# Adafruit_LSM9DS1_Rev_C.net
KiCad netlist of a schematic drawn in EAGLE
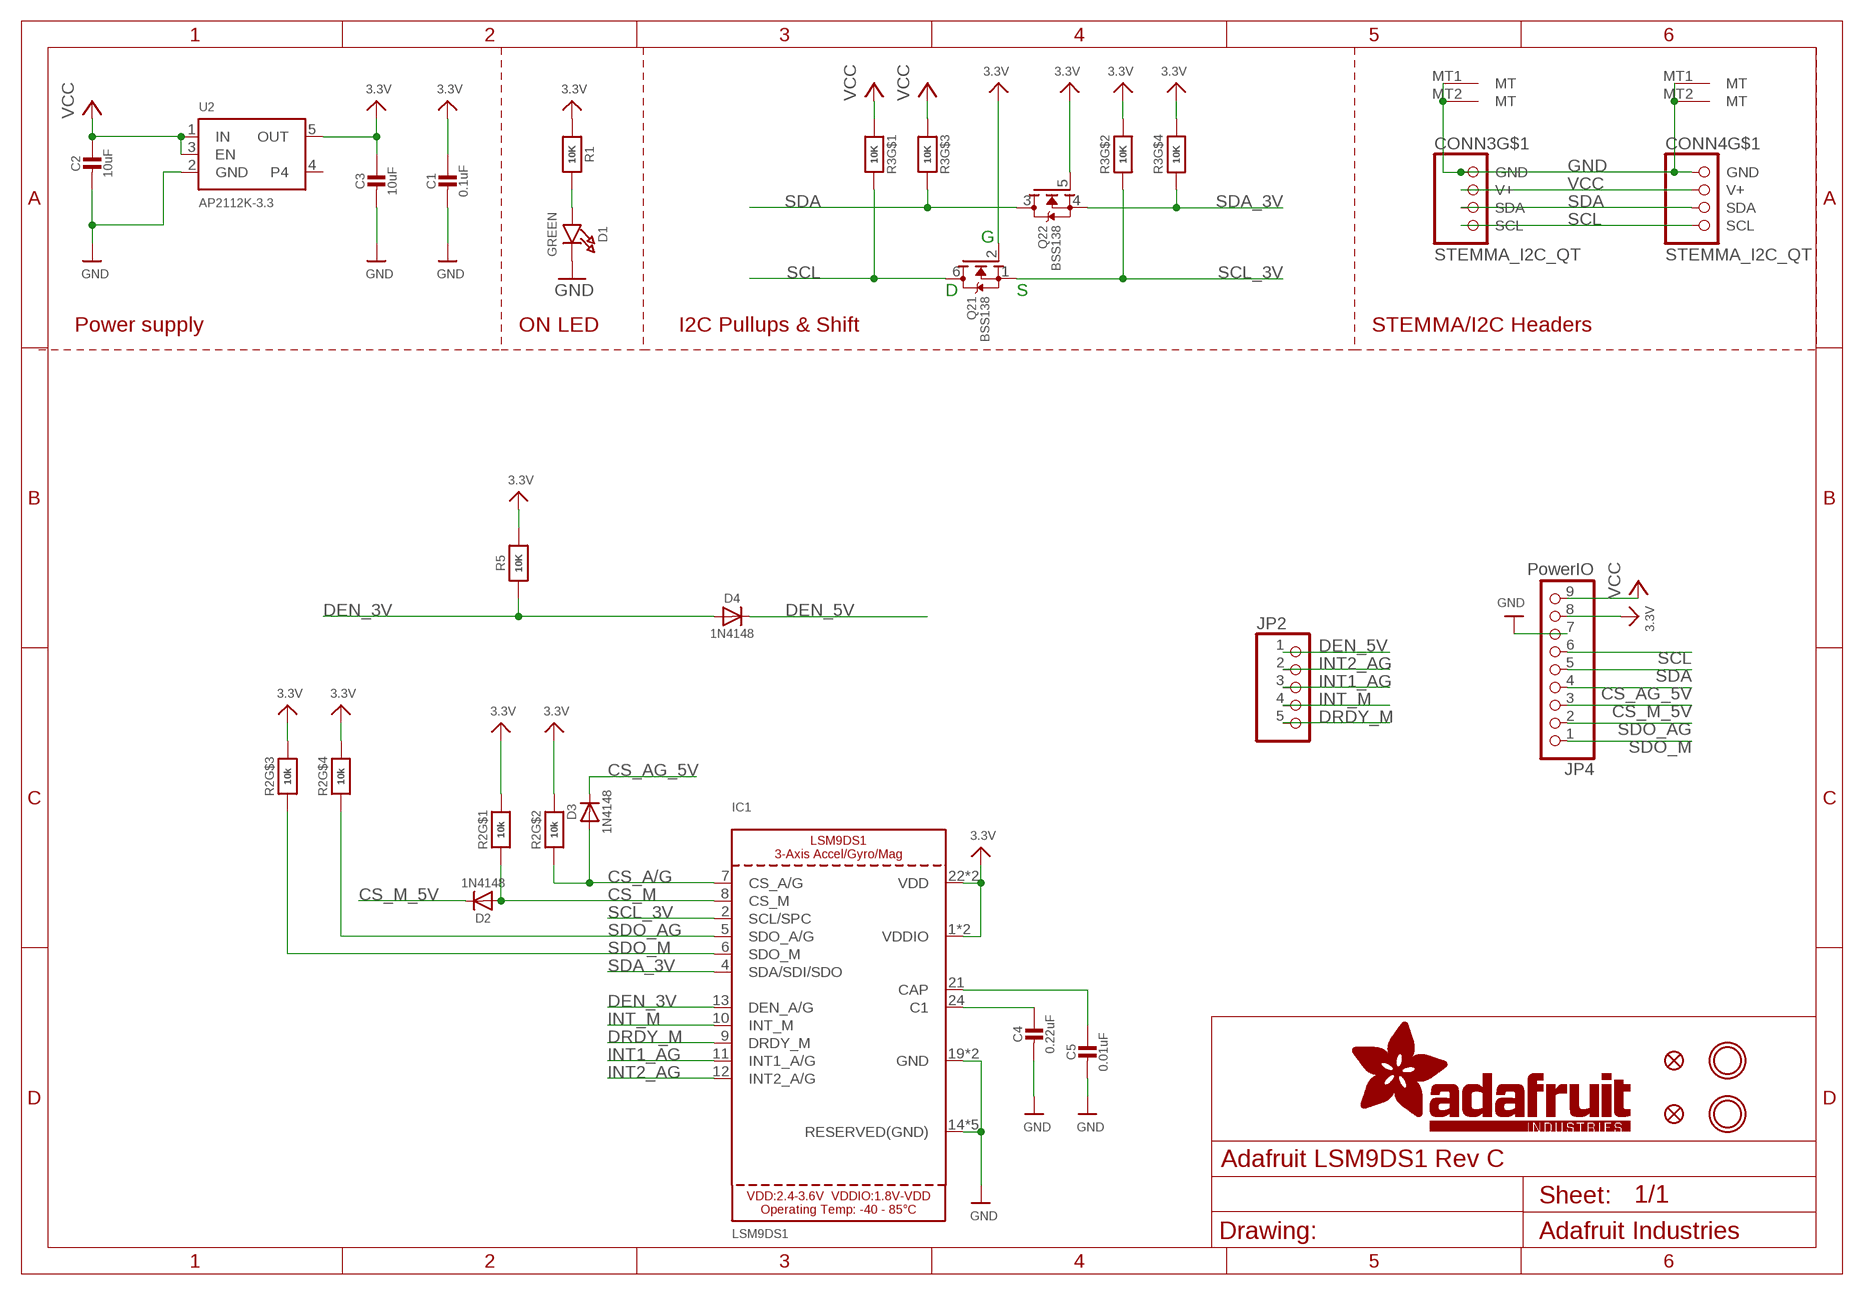
[diagram p0: schematic, sheet 1]

(export (version "E")
  (design (tool "Eeschema 10.0.6"))
  (components
    (comp (ref "C1")
      (value "0.1uF")
      (footprint "eagle-import:0603-NO")
      (libsource (lib "eagle-import") (part "CAP_CERAMIC0603_NO"))
    )
    (comp (ref "C2")
      (value "10uF")
      (footprint "eagle-import:_0805MP")
      (libsource (lib "eagle-import") (part "CAP_CERAMIC_0805MP"))
    )
    (comp (ref "C3")
      (value "10uF")
      (footprint "eagle-import:0805-NO")
      (libsource (lib "eagle-import") (part "CAP_CERAMIC0805-NOOUTLINE"))
    )
    (comp (ref "C4")
      (value "0.22uF")
      (footprint "eagle-import:0603-NO")
      (libsource (lib "eagle-import") (part "CAP_CERAMIC0603_NO"))
    )
    (comp (ref "C5")
      (value "0.01uF")
      (footprint "eagle-import:0603-NO")
      (libsource (lib "eagle-import") (part "CAP_CERAMIC0603_NO"))
    )
    (comp (ref "CONN3")
      (value "STEMMA_I2C_QT")
      (footprint "eagle-import:JST_SH4")
      (libsource (lib "eagle-import") (part "STEMMA_I2C_QT"))
    )
    (comp (ref "CONN4")
      (value "STEMMA_I2C_QT")
      (footprint "eagle-import:JST_SH4")
      (libsource (lib "eagle-import") (part "STEMMA_I2C_QT"))
    )
    (comp (ref "D1")
      (value "GREEN")
      (footprint "eagle-import:CHIPLED_0603_NOOUTLINE")
      (libsource (lib "eagle-import") (part "LED0603_NOOUTLINE"))
    )
    (comp (ref "D2")
      (value "1N4148")
      (footprint "eagle-import:SOD-323")
      (libsource (lib "eagle-import") (part "DIODESOD-323"))
    )
    (comp (ref "D3")
      (value "1N4148")
      (footprint "eagle-import:SOD-323")
      (libsource (lib "eagle-import") (part "DIODESOD-323"))
    )
    (comp (ref "D4")
      (value "1N4148")
      (footprint "eagle-import:SOD-323")
      (libsource (lib "eagle-import") (part "DIODESOD-323"))
    )
    (comp (ref "FID3")
      (value "FIDUCIAL_1MM")
      (footprint "eagle-import:FIDUCIAL_1MM")
      (libsource (lib "eagle-import") (part "FIDUCIAL_1MM"))
    )
    (comp (ref "FID4")
      (value "FIDUCIAL_1MM")
      (footprint "eagle-import:FIDUCIAL_1MM")
      (libsource (lib "eagle-import") (part "FIDUCIAL_1MM"))
    )
    (comp (ref "IC1")
      (value "LSM9DS1")
      (footprint "eagle-import:LGA24_3.5X3.1MM")
      (libsource (lib "eagle-import") (part "LSM9DS1"))
    )
    (comp (ref "JP2")
      (value "HEADER-1X570MIL")
      (footprint "eagle-import:1X05_ROUND_70")
      (libsource (lib "eagle-import") (part "HEADER-1X570MIL"))
    )
    (comp (ref "JP4")
      (value "PowerIO")
      (footprint "eagle-import:1X09_ROUND_70")
      (libsource (lib "eagle-import") (part "HEADER-1X970MIL"))
    )
    (comp (ref "Q2")
      (value "BSS138")
      (footprint "eagle-import:SOT363")
      (libsource (lib "eagle-import") (part "MOSFET-N_DUAL"))
    )
    (comp (ref "R1")
      (value "10K")
      (footprint "eagle-import:0603-NO")
      (libsource (lib "eagle-import") (part "RESISTOR_0603_NOOUT"))
    )
    (comp (ref "R2")
      (value "10k")
      (footprint "eagle-import:RESPACK_4X0603")
      (libsource (lib "eagle-import") (part "RESISTOR_4PACK"))
    )
    (comp (ref "R3")
      (value "10K")
      (footprint "eagle-import:RESPACK_4X0603")
      (libsource (lib "eagle-import") (part "RESISTOR_4PACK"))
    )
    (comp (ref "R5")
      (value "10K")
      (footprint "eagle-import:0603-NO")
      (libsource (lib "eagle-import") (part "RESISTOR_0603_NOOUT"))
    )
    (comp (ref "U$1")
      (value "MOUNTINGHOLE2.5")
      (footprint "eagle-import:MOUNTINGHOLE_2.5_PLATED")
      (libsource (lib "eagle-import") (part "MOUNTINGHOLE2.5"))
    )
    (comp (ref "U$17")
      (value "MOUNTINGHOLE2.5")
      (footprint "eagle-import:MOUNTINGHOLE_2.5_PLATED")
      (libsource (lib "eagle-import") (part "MOUNTINGHOLE2.5"))
    )
    (comp (ref "U2")
      (value "AP2112K-3.3")
      (footprint "eagle-import:SOT23-5")
      (libsource (lib "eagle-import") (part "VREG_SOT23-5"))
    )
  )
  (nets
    (net (code "1") (name "/CS_AG_5V") (class "Default")
      (node (ref "D3") (pin "C") (pinfunction "C_C") (pintype "passive"))
      (node (ref "JP4") (pin "4") (pinfunction "4_4") (pintype "passive"))
    )
    (net (code "2") (name "/CS_A{slash}G") (class "Default")
      (node (ref "D3") (pin "A") (pinfunction "A_A") (pintype "passive"))
      (node (ref "IC1") (pin "7") (pinfunction "CS_A/G_7") (pintype "bidirectional"))
      (node (ref "R2") (pin "2") (pinfunction "1_2") (pintype "passive"))
    )
    (net (code "3") (name "/CS_M") (class "Default")
      (node (ref "D2") (pin "A") (pinfunction "A_A") (pintype "passive"))
      (node (ref "IC1") (pin "8") (pinfunction "CS_M_8") (pintype "bidirectional"))
      (node (ref "R2") (pin "1") (pinfunction "1_1") (pintype "passive"))
    )
    (net (code "4") (name "/CS_M_5V") (class "Default")
      (node (ref "D2") (pin "C") (pinfunction "C_C") (pintype "passive"))
      (node (ref "JP4") (pin "3") (pinfunction "3_3") (pintype "passive"))
    )
    (net (code "5") (name "/DEN_3V") (class "Default")
      (node (ref "D4") (pin "A") (pinfunction "A_A") (pintype "passive"))
      (node (ref "IC1") (pin "13") (pinfunction "DEN_A/G_13") (pintype "bidirectional"))
      (node (ref "R5") (pin "1") (pinfunction "1_1") (pintype "passive"))
    )
    (net (code "6") (name "/DEN_5V") (class "Default")
      (node (ref "D4") (pin "C") (pinfunction "C_C") (pintype "passive"))
      (node (ref "JP2") (pin "1") (pinfunction "1_1") (pintype "passive"))
    )
    (net (code "7") (name "/DRDY_M") (class "Default")
      (node (ref "IC1") (pin "9") (pinfunction "DRDY_M_9") (pintype "bidirectional"))
      (node (ref "JP2") (pin "5") (pinfunction "5_5") (pintype "passive"))
    )
    (net (code "8") (name "/INT1_AG") (class "Default")
      (node (ref "IC1") (pin "11") (pinfunction "INT1_A/G_11") (pintype "bidirectional"))
      (node (ref "JP2") (pin "3") (pinfunction "3_3") (pintype "passive"))
    )
    (net (code "9") (name "/INT2_AG") (class "Default")
      (node (ref "IC1") (pin "12") (pinfunction "INT2_A/G_12") (pintype "bidirectional"))
      (node (ref "JP2") (pin "2") (pinfunction "2_2") (pintype "passive"))
    )
    (net (code "10") (name "/INT_M") (class "Default")
      (node (ref "IC1") (pin "10") (pinfunction "INT_M_10") (pintype "bidirectional"))
      (node (ref "JP2") (pin "4") (pinfunction "4_4") (pintype "passive"))
    )
    (net (code "11") (name "/SCL") (class "Default")
      (node (ref "CONN3") (pin "4") (pinfunction "SCL_4") (pintype "passive"))
      (node (ref "CONN4") (pin "4") (pinfunction "SCL_4") (pintype "passive"))
      (node (ref "JP4") (pin "6") (pinfunction "6_6") (pintype "passive"))
      (node (ref "Q2") (pin "6") (pinfunction "D_6") (pintype "bidirectional"))
      (node (ref "R3") (pin "8") (pinfunction "2_8") (pintype "passive"))
    )
    (net (code "12") (name "/SCL_3V") (class "Default")
      (node (ref "IC1") (pin "2") (pinfunction "SCL/SPC_2") (pintype "bidirectional"))
      (node (ref "Q2") (pin "1") (pinfunction "S_1") (pintype "bidirectional"))
      (node (ref "R3") (pin "7") (pinfunction "2_7") (pintype "passive"))
    )
    (net (code "13") (name "/SDA") (class "Default")
      (node (ref "CONN3") (pin "3") (pinfunction "SDA_3") (pintype "passive"))
      (node (ref "CONN4") (pin "3") (pinfunction "SDA_3") (pintype "passive"))
      (node (ref "JP4") (pin "5") (pinfunction "5_5") (pintype "passive"))
      (node (ref "Q2") (pin "3") (pinfunction "D_3") (pintype "bidirectional"))
      (node (ref "R3") (pin "6") (pinfunction "2_6") (pintype "passive"))
    )
    (net (code "14") (name "/SDA_3V") (class "Default")
      (node (ref "IC1") (pin "4") (pinfunction "SDA/SDI/SDO_4") (pintype "bidirectional"))
      (node (ref "Q2") (pin "4") (pinfunction "S_4") (pintype "bidirectional"))
      (node (ref "R3") (pin "5") (pinfunction "2_5") (pintype "passive"))
    )
    (net (code "15") (name "/SDO_AG") (class "Default")
      (node (ref "IC1") (pin "5") (pinfunction "SDO_A/G_5") (pintype "bidirectional"))
      (node (ref "JP4") (pin "2") (pinfunction "2_2") (pintype "passive"))
      (node (ref "R2") (pin "4") (pinfunction "1_4") (pintype "passive"))
    )
    (net (code "16") (name "/SDO_M") (class "Default")
      (node (ref "IC1") (pin "6") (pinfunction "SDO_M_6") (pintype "bidirectional"))
      (node (ref "JP4") (pin "1") (pinfunction "1_1") (pintype "passive"))
      (node (ref "R2") (pin "3") (pinfunction "1_3") (pintype "passive"))
    )
    (net (code "17") (name "3.3V") (class "Default")
      (node (ref "C1") (pin "1") (pinfunction "1_1") (pintype "passive"))
      (node (ref "C3") (pin "1") (pinfunction "1_1") (pintype "passive"))
      (node (ref "IC1") (pin "1") (pinfunction "VDDIO_1") (pintype "power_in"))
      (node (ref "IC1") (pin "22") (pinfunction "VDD_22") (pintype "power_in"))
      (node (ref "IC1") (pin "23") (pinfunction "VDD_23") (pintype "power_in"))
      (node (ref "IC1") (pin "3") (pinfunction "VDDIO_3") (pintype "power_in"))
      (node (ref "JP4") (pin "8") (pinfunction "8_8") (pintype "passive"))
      (node (ref "Q2") (pin "2") (pinfunction "G_2") (pintype "bidirectional"))
      (node (ref "Q2") (pin "5") (pinfunction "G_5") (pintype "bidirectional"))
      (node (ref "R1") (pin "1") (pinfunction "1_1") (pintype "passive"))
      (node (ref "R2") (pin "5") (pinfunction "2_5") (pintype "passive"))
      (node (ref "R2") (pin "6") (pinfunction "2_6") (pintype "passive"))
      (node (ref "R2") (pin "7") (pinfunction "2_7") (pintype "passive"))
      (node (ref "R2") (pin "8") (pinfunction "2_8") (pintype "passive"))
      (node (ref "R3") (pin "2") (pinfunction "1_2") (pintype "passive"))
      (node (ref "R3") (pin "4") (pinfunction "1_4") (pintype "passive"))
      (node (ref "R5") (pin "2") (pinfunction "2_2") (pintype "passive"))
      (node (ref "U2") (pin "5") (pinfunction "OUT_5") (pintype "power_in"))
    )
    (net (code "18") (name "GND") (class "Default")
      (node (ref "C1") (pin "2") (pinfunction "2_2") (pintype "passive"))
      (node (ref "C2") (pin "2") (pinfunction "2_2") (pintype "passive"))
      (node (ref "C3") (pin "2") (pinfunction "2_2") (pintype "passive"))
      (node (ref "C4") (pin "2") (pinfunction "2_2") (pintype "passive"))
      (node (ref "C5") (pin "2") (pinfunction "2_2") (pintype "passive"))
      (node (ref "CONN3") (pin "1") (pinfunction "GND_1") (pintype "passive"))
      (node (ref "CONN3") (pin "MT1") (pinfunction "MT_MT1") (pintype "bidirectional"))
      (node (ref "CONN3") (pin "MT2") (pinfunction "MT_MT2") (pintype "bidirectional"))
      (node (ref "CONN4") (pin "1") (pinfunction "GND_1") (pintype "passive"))
      (node (ref "CONN4") (pin "MT1") (pinfunction "MT_MT1") (pintype "bidirectional"))
      (node (ref "CONN4") (pin "MT2") (pinfunction "MT_MT2") (pintype "bidirectional"))
      (node (ref "D1") (pin "C") (pinfunction "C_C") (pintype "passive"))
      (node (ref "IC1") (pin "14") (pinfunction "RESERVED(GND)_14") (pintype "power_in"))
      (node (ref "IC1") (pin "15") (pinfunction "RESERVED(GND)_15") (pintype "power_in"))
      (node (ref "IC1") (pin "16") (pinfunction "RESERVED(GND)_16") (pintype "power_in"))
      (node (ref "IC1") (pin "17") (pinfunction "RESERVED(GND)_17") (pintype "power_in"))
      (node (ref "IC1") (pin "18") (pinfunction "RESERVED(GND)_18") (pintype "power_in"))
      (node (ref "IC1") (pin "19") (pinfunction "GND_19") (pintype "power_in"))
      (node (ref "IC1") (pin "20") (pinfunction "GND_20") (pintype "power_in"))
      (node (ref "JP4") (pin "7") (pinfunction "7_7") (pintype "passive"))
      (node (ref "U2") (pin "2") (pinfunction "GND_2") (pintype "power_in"))
    )
    (net (code "19") (name "Net-(D1-PadA)") (class "Default")
      (node (ref "D1") (pin "A") (pinfunction "A_A") (pintype "passive"))
      (node (ref "R1") (pin "2") (pinfunction "2_2") (pintype "passive"))
    )
    (net (code "20") (name "Net-(IC1-C1)") (class "Default")
      (node (ref "C4") (pin "1") (pinfunction "1_1") (pintype "passive"))
      (node (ref "IC1") (pin "24") (pinfunction "C1_24") (pintype "bidirectional"))
    )
    (net (code "21") (name "Net-(IC1-CAP)") (class "Default")
      (node (ref "C5") (pin "1") (pinfunction "1_1") (pintype "passive"))
      (node (ref "IC1") (pin "21") (pinfunction "CAP_21") (pintype "bidirectional"))
    )
    (net (code "22") (name "VCC") (class "Default")
      (node (ref "C2") (pin "1") (pinfunction "1_1") (pintype "passive"))
      (node (ref "CONN3") (pin "2") (pinfunction "V+_2") (pintype "passive"))
      (node (ref "CONN4") (pin "2") (pinfunction "V+_2") (pintype "passive"))
      (node (ref "JP4") (pin "9") (pinfunction "9_9") (pintype "passive"))
      (node (ref "R3") (pin "1") (pinfunction "1_1") (pintype "passive"))
      (node (ref "R3") (pin "3") (pinfunction "1_3") (pintype "passive"))
      (node (ref "U2") (pin "1") (pinfunction "IN_1") (pintype "power_in"))
      (node (ref "U2") (pin "3") (pinfunction "EN_3") (pintype "input"))
    )
    (net (code "23") (name "unconnected-(U2-P4-Pad4)") (class "Default")
      (node (ref "U2") (pin "4") (pinfunction "P4_4") (pintype "bidirectional"))
    )
  )
)
